# Own_Multi_Display_Board_dev_v1_0_Final_A.net
KiCad netlist of a schematic drawn in EAGLE
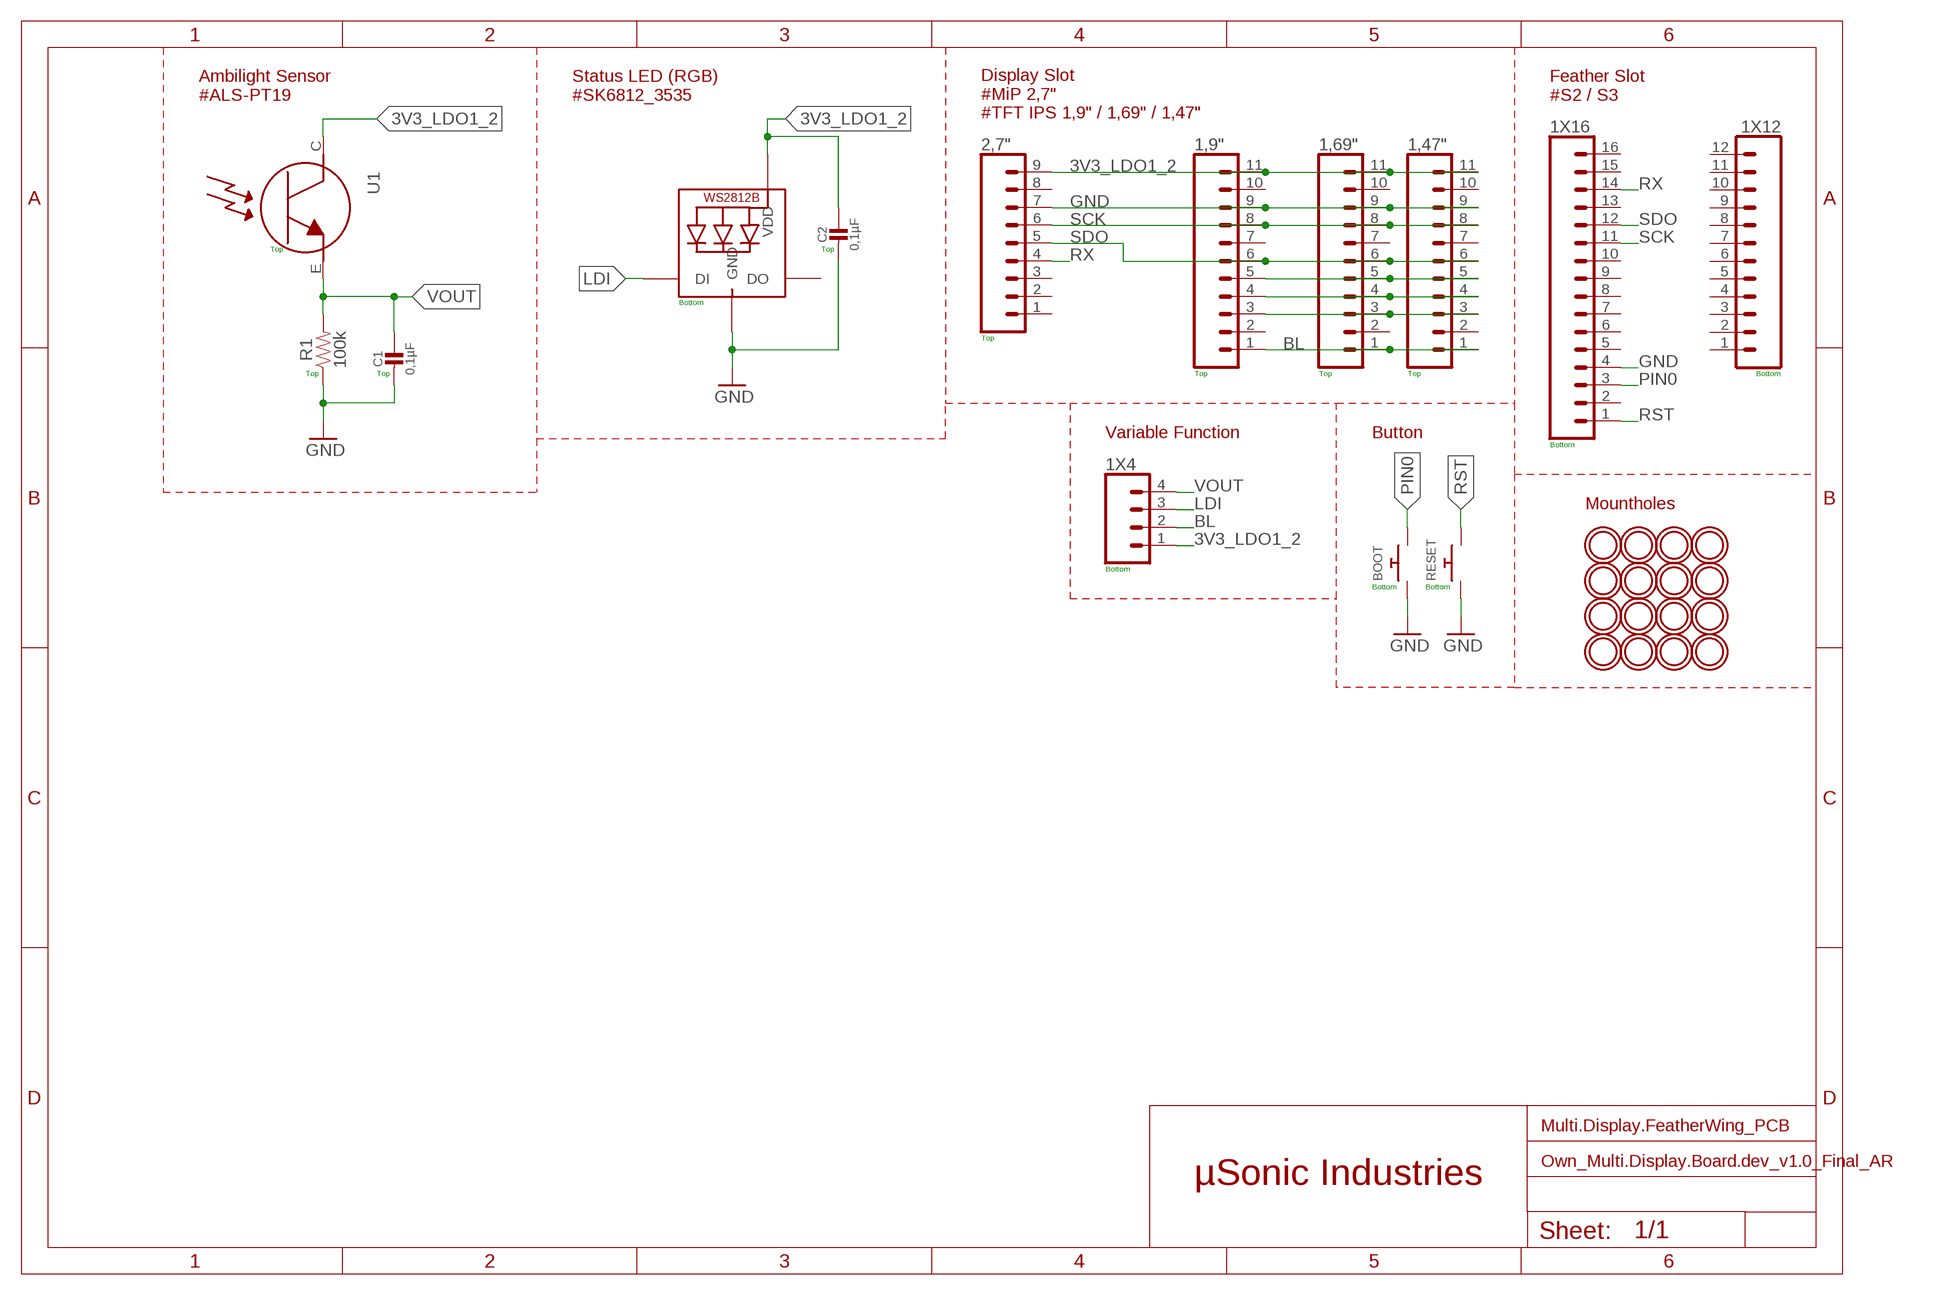
[diagram p0: schematic, sheet 1]

(export (version "E")
  (design (tool "Eeschema 10.0.6"))
  (components
    (comp (ref "1,9\"")
      (value "CONN_111X11_NO_SILK")
      (footprint "eagle-import:1X11_NO_SILK")
      (libsource (lib "eagle-import") (part "CONN_111X11_NO_SILK"))
    )
    (comp (ref "1,47\"")
      (value "CONN_111X11_NO_SILK")
      (footprint "eagle-import:1X11_NO_SILK")
      (libsource (lib "eagle-import") (part "CONN_111X11_NO_SILK"))
    )
    (comp (ref "1,69\"")
      (value "CONN_111X11_NO_SILK")
      (footprint "eagle-import:1X11_NO_SILK")
      (libsource (lib "eagle-import") (part "CONN_111X11_NO_SILK"))
    )
    (comp (ref "1X4")
      (value "CONN_041X04_NO_SILK")
      (footprint "eagle-import:1X04_NO_SILK")
      (libsource (lib "eagle-import") (part "CONN_041X04_NO_SILK"))
    )
    (comp (ref "1X12")
      (value "CONN_12NO_SILK")
      (footprint "eagle-import:1X12_NO_SILK")
      (libsource (lib "eagle-import") (part "CONN_12NO_SILK"))
    )
    (comp (ref "1X16")
      (value "CONN_161X16_NO_SILK")
      (footprint "eagle-import:1X16_NO_SILK")
      (libsource (lib "eagle-import") (part "CONN_161X16_NO_SILK"))
    )
    (comp (ref "2,7\"")
      (value "CONN_09NO_SILK")
      (footprint "eagle-import:1X09_NO_SILK")
      (libsource (lib "eagle-import") (part "CONN_09NO_SILK"))
    )
    (comp (ref "BOOT")
      (value "SWITCH_PUSHBUTTONSF_OWN")
      (footprint "eagle-import:OWN_TACT_PANA-EVQ")
      (libsource (lib "eagle-import") (part "SWITCH_PUSHBUTTONSF_OWN"))
    )
    (comp (ref "C1")
      (value "0,1µF")
      (footprint "eagle-import:MICROBUILDER_0805_10MGAP")
      (libsource (lib "eagle-import") (part "MICROBUILDER_CAP_CERAMIC0805_10MGAP"))
    )
    (comp (ref "C2")
      (value "0,1µF")
      (footprint "eagle-import:MICROBUILDER_0805_10MGAP")
      (libsource (lib "eagle-import") (part "MICROBUILDER_CAP_CERAMIC0805_10MGAP"))
    )
    (comp (ref "LED1")
      (value "MICROBUILDER_WS2812B_SK6812E")
      (footprint "eagle-import:MICROBUILDER_NEO3535_REVERSE")
      (libsource (lib "eagle-import") (part "MICROBUILDER_WS2812B_SK6812E"))
    )
    (comp (ref "R1")
      (value "100k")
      (footprint "eagle-import:0805")
      (libsource (lib "eagle-import") (part "RESISTOR0805"))
    )
    (comp (ref "RESET")
      (value "SWITCH_PUSHBUTTONSF_OWN")
      (footprint "eagle-import:OWN_TACT_PANA-EVQ")
      (libsource (lib "eagle-import") (part "SWITCH_PUSHBUTTONSF_OWN"))
    )
    (comp (ref "U$5")
      (value "MOUNTINGHOLE2.5")
      (footprint "eagle-import:MOUNTINGHOLE_2.5_PLATED")
      (libsource (lib "eagle-import") (part "MOUNTINGHOLE2.5"))
    )
    (comp (ref "U$8")
      (value "MOUNTINGHOLE2.5")
      (footprint "eagle-import:MOUNTINGHOLE_2.5_PLATED")
      (libsource (lib "eagle-import") (part "MOUNTINGHOLE2.5"))
    )
    (comp (ref "U$16")
      (value "MOUNTINGHOLE2.5")
      (footprint "eagle-import:MOUNTINGHOLE_2.5_PLATED")
      (libsource (lib "eagle-import") (part "MOUNTINGHOLE2.5"))
    )
    (comp (ref "U$18")
      (value "MOUNTINGHOLE2.5")
      (footprint "eagle-import:MOUNTINGHOLE_2.5_PLATED")
      (libsource (lib "eagle-import") (part "MOUNTINGHOLE2.5"))
    )
    (comp (ref "U$19")
      (value "MOUNTINGHOLE2.5")
      (footprint "eagle-import:MOUNTINGHOLE_2.5_PLATED")
      (libsource (lib "eagle-import") (part "MOUNTINGHOLE2.5"))
    )
    (comp (ref "U$23")
      (value "MOUNTINGHOLE2.5")
      (footprint "eagle-import:MOUNTINGHOLE_2.5_PLATED")
      (libsource (lib "eagle-import") (part "MOUNTINGHOLE2.5"))
    )
    (comp (ref "U$24")
      (value "MOUNTINGHOLE2.5")
      (footprint "eagle-import:MOUNTINGHOLE_2.5_PLATED")
      (libsource (lib "eagle-import") (part "MOUNTINGHOLE2.5"))
    )
    (comp (ref "U$25")
      (value "MOUNTINGHOLE2.5")
      (footprint "eagle-import:MOUNTINGHOLE_2.5_PLATED")
      (libsource (lib "eagle-import") (part "MOUNTINGHOLE2.5"))
    )
    (comp (ref "U$26")
      (value "MOUNTINGHOLE2.5")
      (footprint "eagle-import:MOUNTINGHOLE_2.5_PLATED")
      (libsource (lib "eagle-import") (part "MOUNTINGHOLE2.5"))
    )
    (comp (ref "U$27")
      (value "MOUNTINGHOLE2.5")
      (footprint "eagle-import:MOUNTINGHOLE_2.5_PLATED")
      (libsource (lib "eagle-import") (part "MOUNTINGHOLE2.5"))
    )
    (comp (ref "U$28")
      (value "MOUNTINGHOLE2.5")
      (footprint "eagle-import:MOUNTINGHOLE_2.5_PLATED")
      (libsource (lib "eagle-import") (part "MOUNTINGHOLE2.5"))
    )
    (comp (ref "U$29")
      (value "MOUNTINGHOLE2.5")
      (footprint "eagle-import:MOUNTINGHOLE_2.5_PLATED")
      (libsource (lib "eagle-import") (part "MOUNTINGHOLE2.5"))
    )
    (comp (ref "U$30")
      (value "MOUNTINGHOLE2.5")
      (footprint "eagle-import:MOUNTINGHOLE_2.5_PLATED")
      (libsource (lib "eagle-import") (part "MOUNTINGHOLE2.5"))
    )
    (comp (ref "U$31")
      (value "MOUNTINGHOLE2.5")
      (footprint "eagle-import:MOUNTINGHOLE_2.5_PLATED")
      (libsource (lib "eagle-import") (part "MOUNTINGHOLE2.5"))
    )
    (comp (ref "U$32")
      (value "MOUNTINGHOLE2.5")
      (footprint "eagle-import:MOUNTINGHOLE_2.5_PLATED")
      (libsource (lib "eagle-import") (part "MOUNTINGHOLE2.5"))
    )
    (comp (ref "U$33")
      (value "MOUNTINGHOLE2.5")
      (footprint "eagle-import:MOUNTINGHOLE_2.5_PLATED")
      (libsource (lib "eagle-import") (part "MOUNTINGHOLE2.5"))
    )
    (comp (ref "U1")
      (value "MICROBUILDER_LIGHT_ALS-PT19-315C")
      (footprint "eagle-import:MICROBUILDER_ALS-PT19-315C")
      (libsource (lib "eagle-import") (part "MICROBUILDER_LIGHT_ALS-PT19-315C"))
    )
  )
  (nets
    (net (code "1") (name "/BL") (class "Default")
      (node (ref "1,47\"") (pin "1") (pinfunction "1_1") (pintype "passive"))
      (node (ref "1,69\"") (pin "1") (pinfunction "1_1") (pintype "passive"))
      (node (ref "1,9\"") (pin "1") (pinfunction "1_1") (pintype "passive"))
      (node (ref "1X4") (pin "2") (pinfunction "2_2") (pintype "passive"))
    )
    (net (code "2") (name "/RX") (class "Default")
      (node (ref "1X16") (pin "14") (pinfunction "14_14") (pintype "passive"))
      (node (ref "2,7\"") (pin "4") (pinfunction "4_4") (pintype "passive"))
    )
    (net (code "3") (name "/SCK") (class "Default")
      (node (ref "1,47\"") (pin "8") (pinfunction "8_8") (pintype "passive"))
      (node (ref "1,69\"") (pin "8") (pinfunction "8_8") (pintype "passive"))
      (node (ref "1,9\"") (pin "8") (pinfunction "8_8") (pintype "passive"))
      (node (ref "1X16") (pin "11") (pinfunction "11_11") (pintype "passive"))
      (node (ref "2,7\"") (pin "6") (pinfunction "6_6") (pintype "passive"))
    )
    (net (code "4") (name "/SDO") (class "Default")
      (node (ref "1,47\"") (pin "6") (pinfunction "6_6") (pintype "passive"))
      (node (ref "1,69\"") (pin "6") (pinfunction "6_6") (pintype "passive"))
      (node (ref "1,9\"") (pin "6") (pinfunction "6_6") (pintype "passive"))
      (node (ref "1X16") (pin "12") (pinfunction "12_12") (pintype "passive"))
      (node (ref "2,7\"") (pin "5") (pinfunction "5_5") (pintype "passive"))
    )
    (net (code "5") (name "3V3_LDO1_2") (class "Default")
      (node (ref "1,47\"") (pin "11") (pinfunction "11_11") (pintype "passive"))
      (node (ref "1,69\"") (pin "11") (pinfunction "11_11") (pintype "passive"))
      (node (ref "1,9\"") (pin "11") (pinfunction "11_11") (pintype "passive"))
      (node (ref "1X4") (pin "1") (pinfunction "1_1") (pintype "passive"))
      (node (ref "2,7\"") (pin "9") (pinfunction "9_9") (pintype "passive"))
      (node (ref "C2") (pin "1") (pinfunction "1_1") (pintype "passive"))
      (node (ref "LED1") (pin "1-VDD") (pinfunction "VDD_1-VDD") (pintype "power_in"))
      (node (ref "U1") (pin "C") (pinfunction "C_C") (pintype "bidirectional"))
    )
    (net (code "6") (name "GND") (class "Default")
      (node (ref "1,47\"") (pin "9") (pinfunction "9_9") (pintype "passive"))
      (node (ref "1,69\"") (pin "9") (pinfunction "9_9") (pintype "passive"))
      (node (ref "1,9\"") (pin "9") (pinfunction "9_9") (pintype "passive"))
      (node (ref "1X16") (pin "4") (pinfunction "4_4") (pintype "passive"))
      (node (ref "2,7\"") (pin "7") (pinfunction "7_7") (pintype "passive"))
      (node (ref "BOOT") (pin "P$1") (pinfunction "P$1_P$1") (pintype "passive"))
      (node (ref "C1") (pin "2") (pinfunction "2_2") (pintype "passive"))
      (node (ref "C2") (pin "2") (pinfunction "2_2") (pintype "passive"))
      (node (ref "LED1") (pin "3-GND") (pinfunction "GND_3-GND") (pintype "power_in"))
      (node (ref "R1") (pin "1") (pinfunction "1_1") (pintype "passive"))
      (node (ref "RESET") (pin "P$1") (pinfunction "P$1_P$1") (pintype "passive"))
    )
    (net (code "7") (name "LDI") (class "Default")
      (node (ref "1X4") (pin "3") (pinfunction "3_3") (pintype "passive"))
      (node (ref "LED1") (pin "4-DIN") (pinfunction "DI_4-DIN") (pintype "input"))
    )
    (net (code "8") (name "Net-(1,47\"-Pad3)") (class "Default")
      (node (ref "1,47\"") (pin "3") (pinfunction "3_3") (pintype "passive"))
      (node (ref "1,69\"") (pin "3") (pinfunction "3_3") (pintype "passive"))
      (node (ref "1,9\"") (pin "3") (pinfunction "3_3") (pintype "passive"))
    )
    (net (code "9") (name "Net-(1,47\"-Pad4)") (class "Default")
      (node (ref "1,47\"") (pin "4") (pinfunction "4_4") (pintype "passive"))
      (node (ref "1,69\"") (pin "4") (pinfunction "4_4") (pintype "passive"))
      (node (ref "1,9\"") (pin "4") (pinfunction "4_4") (pintype "passive"))
    )
    (net (code "10") (name "Net-(1,47\"-Pad5)") (class "Default")
      (node (ref "1,47\"") (pin "5") (pinfunction "5_5") (pintype "passive"))
      (node (ref "1,69\"") (pin "5") (pinfunction "5_5") (pintype "passive"))
      (node (ref "1,9\"") (pin "5") (pinfunction "5_5") (pintype "passive"))
    )
    (net (code "11") (name "PIN0") (class "Default")
      (node (ref "1X16") (pin "3") (pinfunction "3_3") (pintype "passive"))
      (node (ref "BOOT") (pin "P$2") (pinfunction "P$2_P$2") (pintype "passive"))
    )
    (net (code "12") (name "RST") (class "Default")
      (node (ref "1X16") (pin "1") (pinfunction "1_1") (pintype "passive"))
      (node (ref "RESET") (pin "P$2") (pinfunction "P$2_P$2") (pintype "passive"))
    )
    (net (code "13") (name "VOUT") (class "Default")
      (node (ref "1X4") (pin "4") (pinfunction "4_4") (pintype "passive"))
      (node (ref "C1") (pin "1") (pinfunction "1_1") (pintype "passive"))
      (node (ref "R1") (pin "2") (pinfunction "2_2") (pintype "passive"))
      (node (ref "U1") (pin "E") (pinfunction "E_E") (pintype "bidirectional"))
    )
    (net (code "14") (name "unconnected-(1,9\"-Pad2)") (class "Default")
      (node (ref "1,9\"") (pin "2") (pinfunction "2_2") (pintype "passive"))
    )
    (net (code "15") (name "unconnected-(1,9\"-Pad7)") (class "Default")
      (node (ref "1,9\"") (pin "7") (pinfunction "7_7") (pintype "passive"))
    )
    (net (code "16") (name "unconnected-(1,9\"-Pad10)") (class "Default")
      (node (ref "1,9\"") (pin "10") (pinfunction "10_10") (pintype "passive"))
    )
    (net (code "17") (name "unconnected-(1,47\"-Pad2)") (class "Default")
      (node (ref "1,47\"") (pin "2") (pinfunction "2_2") (pintype "passive"))
    )
    (net (code "18") (name "unconnected-(1,47\"-Pad7)") (class "Default")
      (node (ref "1,47\"") (pin "7") (pinfunction "7_7") (pintype "passive"))
    )
    (net (code "19") (name "unconnected-(1,47\"-Pad10)") (class "Default")
      (node (ref "1,47\"") (pin "10") (pinfunction "10_10") (pintype "passive"))
    )
    (net (code "20") (name "unconnected-(1,69\"-Pad2)") (class "Default")
      (node (ref "1,69\"") (pin "2") (pinfunction "2_2") (pintype "passive"))
    )
    (net (code "21") (name "unconnected-(1,69\"-Pad7)") (class "Default")
      (node (ref "1,69\"") (pin "7") (pinfunction "7_7") (pintype "passive"))
    )
    (net (code "22") (name "unconnected-(1,69\"-Pad10)") (class "Default")
      (node (ref "1,69\"") (pin "10") (pinfunction "10_10") (pintype "passive"))
    )
    (net (code "23") (name "unconnected-(1X12-Pad1)") (class "Default")
      (node (ref "1X12") (pin "1") (pinfunction "1_1") (pintype "passive"))
    )
    (net (code "24") (name "unconnected-(1X12-Pad2)") (class "Default")
      (node (ref "1X12") (pin "2") (pinfunction "2_2") (pintype "passive"))
    )
    (net (code "25") (name "unconnected-(1X12-Pad3)") (class "Default")
      (node (ref "1X12") (pin "3") (pinfunction "3_3") (pintype "passive"))
    )
    (net (code "26") (name "unconnected-(1X12-Pad4)") (class "Default")
      (node (ref "1X12") (pin "4") (pinfunction "4_4") (pintype "passive"))
    )
    (net (code "27") (name "unconnected-(1X12-Pad5)") (class "Default")
      (node (ref "1X12") (pin "5") (pinfunction "5_5") (pintype "passive"))
    )
    (net (code "28") (name "unconnected-(1X12-Pad6)") (class "Default")
      (node (ref "1X12") (pin "6") (pinfunction "6_6") (pintype "passive"))
    )
    (net (code "29") (name "unconnected-(1X12-Pad7)") (class "Default")
      (node (ref "1X12") (pin "7") (pinfunction "7_7") (pintype "passive"))
    )
    (net (code "30") (name "unconnected-(1X12-Pad8)") (class "Default")
      (node (ref "1X12") (pin "8") (pinfunction "8_8") (pintype "passive"))
    )
    (net (code "31") (name "unconnected-(1X12-Pad9)") (class "Default")
      (node (ref "1X12") (pin "9") (pinfunction "9_9") (pintype "passive"))
    )
    (net (code "32") (name "unconnected-(1X12-Pad10)") (class "Default")
      (node (ref "1X12") (pin "10") (pinfunction "10_10") (pintype "passive"))
    )
    (net (code "33") (name "unconnected-(1X12-Pad11)") (class "Default")
      (node (ref "1X12") (pin "11") (pinfunction "11_11") (pintype "passive"))
    )
    (net (code "34") (name "unconnected-(1X12-Pad12)") (class "Default")
      (node (ref "1X12") (pin "12") (pinfunction "12_12") (pintype "passive"))
    )
    (net (code "35") (name "unconnected-(1X16-Pad2)") (class "Default")
      (node (ref "1X16") (pin "2") (pinfunction "2_2") (pintype "passive"))
    )
    (net (code "36") (name "unconnected-(1X16-Pad5)") (class "Default")
      (node (ref "1X16") (pin "5") (pinfunction "5_5") (pintype "passive"))
    )
    (net (code "37") (name "unconnected-(1X16-Pad6)") (class "Default")
      (node (ref "1X16") (pin "6") (pinfunction "6_6") (pintype "passive"))
    )
    (net (code "38") (name "unconnected-(1X16-Pad7)") (class "Default")
      (node (ref "1X16") (pin "7") (pinfunction "7_7") (pintype "passive"))
    )
    (net (code "39") (name "unconnected-(1X16-Pad8)") (class "Default")
      (node (ref "1X16") (pin "8") (pinfunction "8_8") (pintype "passive"))
    )
    (net (code "40") (name "unconnected-(1X16-Pad9)") (class "Default")
      (node (ref "1X16") (pin "9") (pinfunction "9_9") (pintype "passive"))
    )
    (net (code "41") (name "unconnected-(1X16-Pad10)") (class "Default")
      (node (ref "1X16") (pin "10") (pinfunction "10_10") (pintype "passive"))
    )
    (net (code "42") (name "unconnected-(1X16-Pad13)") (class "Default")
      (node (ref "1X16") (pin "13") (pinfunction "13_13") (pintype "passive"))
    )
    (net (code "43") (name "unconnected-(1X16-Pad15)") (class "Default")
      (node (ref "1X16") (pin "15") (pinfunction "15_15") (pintype "passive"))
    )
    (net (code "44") (name "unconnected-(1X16-Pad16)") (class "Default")
      (node (ref "1X16") (pin "16") (pinfunction "16_16") (pintype "passive"))
    )
    (net (code "45") (name "unconnected-(2,7\"-Pad1)") (class "Default")
      (node (ref "2,7\"") (pin "1") (pinfunction "1_1") (pintype "passive"))
    )
    (net (code "46") (name "unconnected-(2,7\"-Pad2)") (class "Default")
      (node (ref "2,7\"") (pin "2") (pinfunction "2_2") (pintype "passive"))
    )
    (net (code "47") (name "unconnected-(2,7\"-Pad3)") (class "Default")
      (node (ref "2,7\"") (pin "3") (pinfunction "3_3") (pintype "passive"))
    )
    (net (code "48") (name "unconnected-(2,7\"-Pad8)") (class "Default")
      (node (ref "2,7\"") (pin "8") (pinfunction "8_8") (pintype "passive"))
    )
    (net (code "49") (name "unconnected-(LED1-DO-Pad2-DOUT)") (class "Default")
      (node (ref "LED1") (pin "2-DOUT") (pinfunction "DO_2-DOUT") (pintype "output"))
    )
  )
)
